# Blinky_Sch.net
KiCad netlist of a schematic drawn in EAGLE
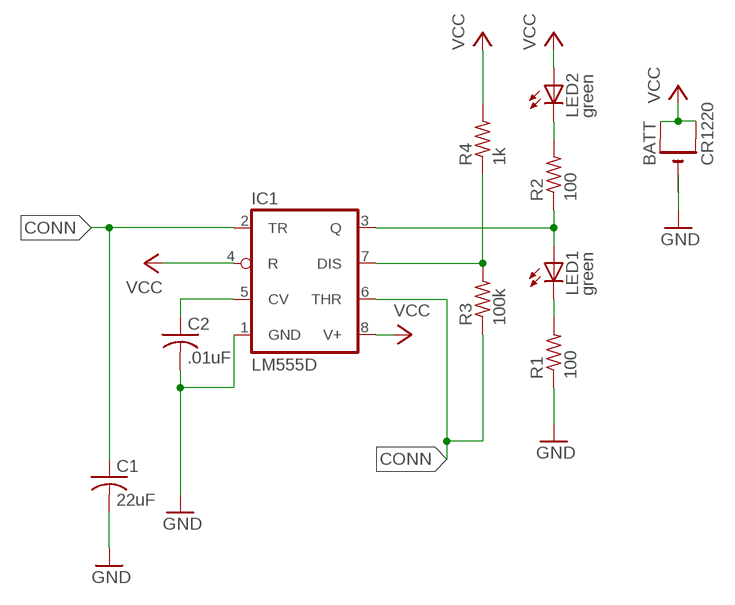
[diagram p0: schematic, sheet 1]

(export (version "E")
  (design (tool "Eeschema 10.0.6"))
  (components
    (comp (ref "BATT")
      (value "CR1220")
      (footprint "eagle-import:CR1220-SMD")
      (fields (field (name "MF") "KEYSTONE") (field (name "MPN") "3080"))
      (libsource (lib "eagle-import") (part "CR1220SMT"))
    )
    (comp (ref "C1")
      (value "22uF")
      (footprint "eagle-import:C0805")
      (libsource (lib "eagle-import") (part "C-USC0805"))
    )
    (comp (ref "C2")
      (value ".01uF")
      (footprint "eagle-import:C0805")
      (libsource (lib "eagle-import") (part "C-USC0805"))
    )
    (comp (ref "IC1")
      (value "LM555D")
      (footprint "eagle-import:SO08")
      (libsource (lib "eagle-import") (part "555DLM"))
    )
    (comp (ref "LED1")
      (value "green")
      (footprint "eagle-import:CHIPLED_0805")
      (libsource (lib "eagle-import") (part "LEDCHIPLED_0805"))
    )
    (comp (ref "LED2")
      (value "green")
      (footprint "eagle-import:CHIPLED_0805")
      (libsource (lib "eagle-import") (part "LEDCHIPLED_0805"))
    )
    (comp (ref "R1")
      (value "100")
      (footprint "eagle-import:R0805")
      (libsource (lib "eagle-import") (part "R-US_R0805"))
    )
    (comp (ref "R2")
      (value "100")
      (footprint "eagle-import:R0805")
      (libsource (lib "eagle-import") (part "R-US_R0805"))
    )
    (comp (ref "R3")
      (value "100k")
      (footprint "eagle-import:R0805")
      (libsource (lib "eagle-import") (part "R-US_R0805"))
    )
    (comp (ref "R4")
      (value "1k")
      (footprint "eagle-import:R0805")
      (libsource (lib "eagle-import") (part "R-US_R0805"))
    )
  )
  (nets
    (net (code "1") (name "CONN") (class "Default")
      (node (ref "C1") (pin "1") (pinfunction "1_1") (pintype "passive"))
      (node (ref "IC1") (pin "2") (pinfunction "TR_2") (pintype "input"))
      (node (ref "IC1") (pin "6") (pinfunction "THR_6") (pintype "input"))
      (node (ref "R3") (pin "1") (pinfunction "1_1") (pintype "passive"))
    )
    (net (code "2") (name "GND") (class "Default")
      (node (ref "C1") (pin "2") (pinfunction "2_2") (pintype "passive"))
      (node (ref "C2") (pin "2") (pinfunction "2_2") (pintype "passive"))
      (node (ref "IC1") (pin "1") (pinfunction "GND_1") (pintype "power_in"))
      (node (ref "R1") (pin "1") (pinfunction "1_1") (pintype "passive"))
    )
    (net (code "3") (name "Net-(IC1-CV)") (class "Default")
      (node (ref "C2") (pin "1") (pinfunction "1_1") (pintype "passive"))
      (node (ref "IC1") (pin "5") (pinfunction "CV_5") (pintype "input"))
    )
    (net (code "4") (name "Net-(IC1-DIS)") (class "Default")
      (node (ref "IC1") (pin "7") (pinfunction "DIS_7") (pintype "input"))
      (node (ref "R3") (pin "2") (pinfunction "2_2") (pintype "passive"))
      (node (ref "R4") (pin "1") (pinfunction "1_1") (pintype "passive"))
    )
    (net (code "5") (name "Net-(IC1-Q)") (class "Default")
      (node (ref "IC1") (pin "3") (pinfunction "Q_3") (pintype "output"))
      (node (ref "LED1") (pin "A") (pinfunction "A_A") (pintype "passive"))
      (node (ref "R2") (pin "1") (pinfunction "1_1") (pintype "passive"))
    )
    (net (code "6") (name "Net-(LED1-PadC)") (class "Default")
      (node (ref "LED1") (pin "C") (pinfunction "C_C") (pintype "passive"))
      (node (ref "R1") (pin "2") (pinfunction "2_2") (pintype "passive"))
    )
    (net (code "7") (name "Net-(LED2-PadC)") (class "Default")
      (node (ref "LED2") (pin "C") (pinfunction "C_C") (pintype "passive"))
      (node (ref "R2") (pin "2") (pinfunction "2_2") (pintype "passive"))
    )
    (net (code "8") (name "VCC") (class "Default")
      (node (ref "BATT") (pin "+$1") (pinfunction "+_+$1") (pintype "passive"))
      (node (ref "BATT") (pin "+$2") (pinfunction "+1_+$2") (pintype "passive"))
      (node (ref "IC1") (pin "4") (pinfunction "R_4") (pintype "input"))
      (node (ref "IC1") (pin "8") (pinfunction "V+_8") (pintype "power_in"))
      (node (ref "LED2") (pin "A") (pinfunction "A_A") (pintype "passive"))
      (node (ref "R4") (pin "2") (pinfunction "2_2") (pintype "passive"))
    )
    (net (code "9") (name "unconnected-(BATT-Pad-)") (class "Default")
      (node (ref "BATT") (pin "-") (pinfunction "-_-") (pintype "passive"))
    )
  )
)
